# DigitalIO.net
KiCad netlist of a schematic drawn in Altium Designer
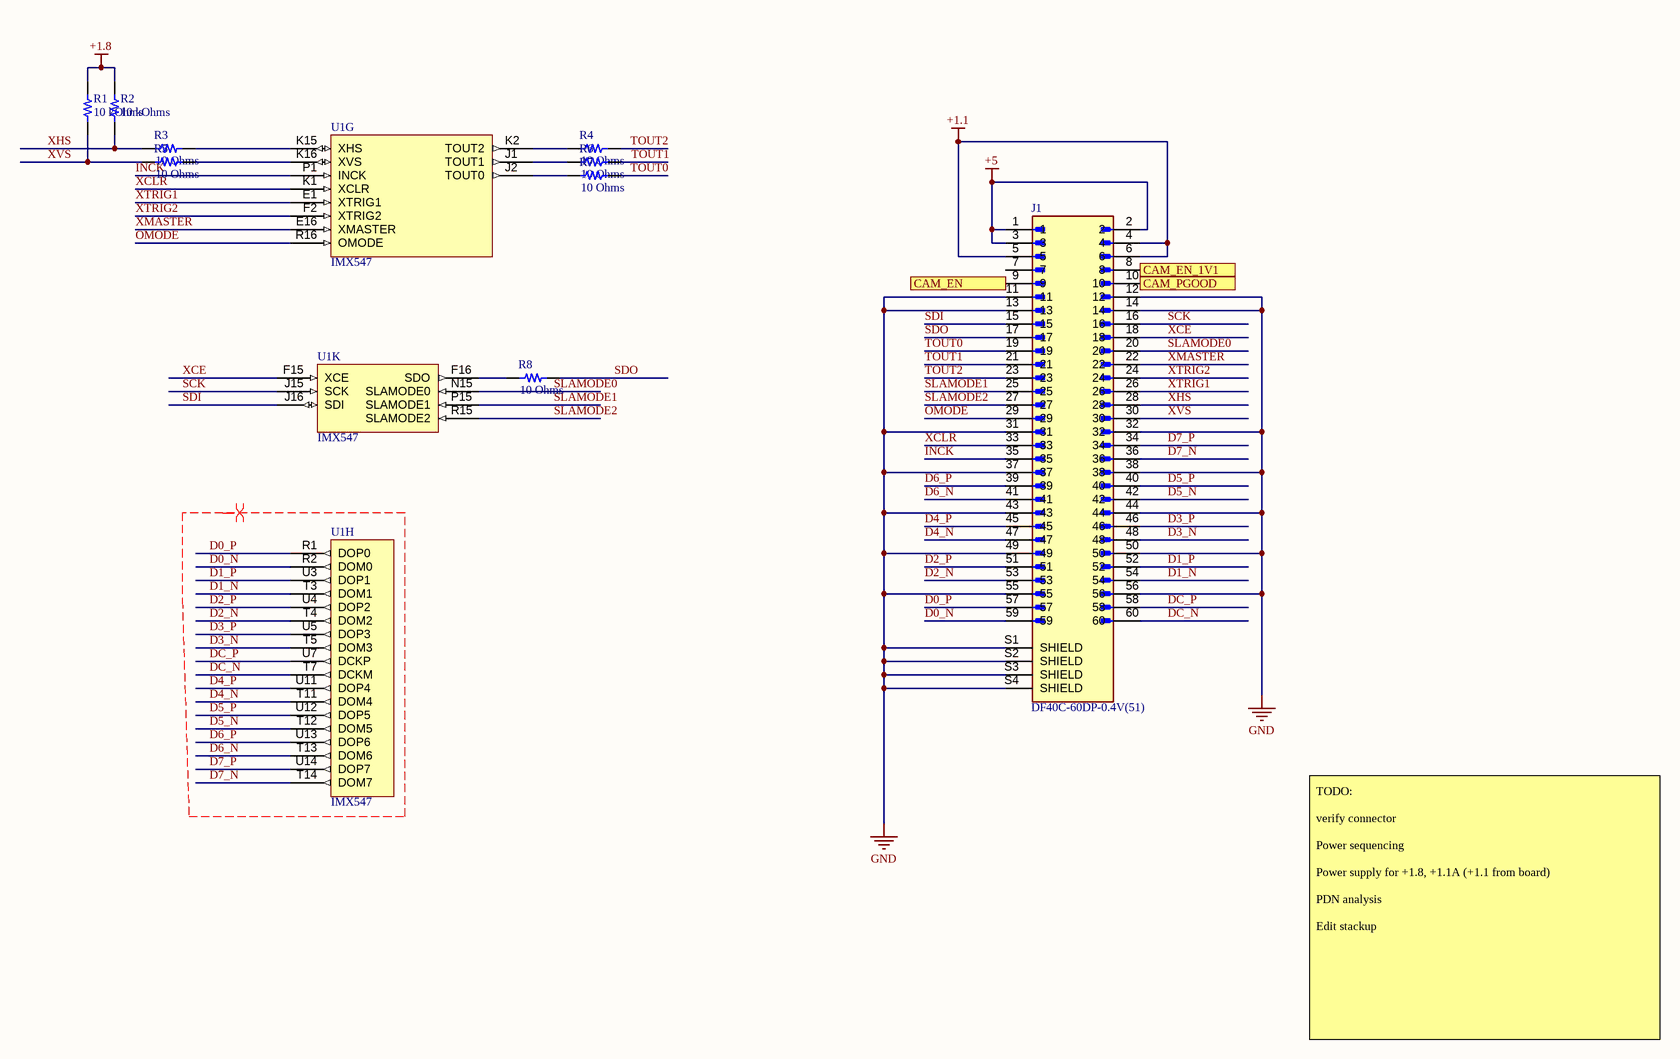
[diagram p0: DigitalIO.SchDoc]

(export (version "E")
  (design (tool "Eeschema 10.0.6"))
  (components
    (comp (ref "J1")
      (value "DF40C-60DP-0.4V(51)")
      (footprint "HIROSE_DF40C-60DP-0.4V(51)")
      (description "60 Position Connector Plug, Outer Shroud Contacts Surface Mount Gold")
      (fields (field (name "MF") "{'manufacturer': u'Hirose Electric'}"))
      (libsource (lib "qwe") (part "DF40C-60DP-0.4V(51)"))
    )
    (comp (ref "R1")
      (value "10 kOhms")
      (footprint "RES 0201_0603")
      (description "RES 10K OHM 5% 1/20W 0201")
      (fields
        (field (name "PART NUMBER") "RMCF0201JG10K0")
        (field (name "MANUFACTURER") "Stackpole Electronics Inc")
      )
      (libsource (lib "Celestial Altium Library - altium_library") (part "Resistor"))
    )
    (comp (ref "R2")
      (value "10 kOhms")
      (footprint "RES 0201_0603")
      (description "RES 10K OHM 5% 1/20W 0201")
      (fields
        (field (name "PART NUMBER") "RMCF0201JG10K0")
        (field (name "MANUFACTURER") "Stackpole Electronics Inc")
      )
      (libsource (lib "Celestial Altium Library - altium_library") (part "Resistor"))
    )
    (comp (ref "R3")
      (value "10 Ohms")
      (footprint "RES 0201_0603")
      (description "RES SMD 10 OHM 1% 1/20W 0201")
      (fields
        (field (name "PART NUMBER") "CRG0201F10R")
        (field (name "MANUFACTURER") "TE Connectivity Passive Product")
      )
      (libsource (lib "Celestial Altium Library - altium_library") (part "Resistor"))
    )
    (comp (ref "R4")
      (value "10 Ohms")
      (footprint "RES 0201_0603")
      (description "RES SMD 10 OHM 1% 1/20W 0201")
      (fields
        (field (name "PART NUMBER") "CRG0201F10R")
        (field (name "MANUFACTURER") "TE Connectivity Passive Product")
      )
      (libsource (lib "Celestial Altium Library - altium_library") (part "Resistor"))
    )
    (comp (ref "R5")
      (value "10 Ohms")
      (footprint "RES 0201_0603")
      (description "RES SMD 10 OHM 1% 1/20W 0201")
      (fields
        (field (name "PART NUMBER") "CRG0201F10R")
        (field (name "MANUFACTURER") "TE Connectivity Passive Product")
      )
      (libsource (lib "Celestial Altium Library - altium_library") (part "Resistor"))
    )
    (comp (ref "R6")
      (value "10 Ohms")
      (footprint "RES 0201_0603")
      (description "RES SMD 10 OHM 1% 1/20W 0201")
      (fields
        (field (name "PART NUMBER") "CRG0201F10R")
        (field (name "MANUFACTURER") "TE Connectivity Passive Product")
      )
      (libsource (lib "Celestial Altium Library - altium_library") (part "Resistor"))
    )
    (comp (ref "R7")
      (value "10 Ohms")
      (footprint "RES 0201_0603")
      (description "RES SMD 10 OHM 1% 1/20W 0201")
      (fields
        (field (name "PART NUMBER") "CRG0201F10R")
        (field (name "MANUFACTURER") "TE Connectivity Passive Product")
      )
      (libsource (lib "Celestial Altium Library - altium_library") (part "Resistor"))
    )
    (comp (ref "R8")
      (value "10 Ohms")
      (footprint "RES 0201_0603")
      (description "RES SMD 10 OHM 1% 1/20W 0201")
      (fields
        (field (name "PART NUMBER") "CRG0201F10R")
        (field (name "MANUFACTURER") "TE Connectivity Passive Product")
      )
      (libsource (lib "Celestial Altium Library - altium_library") (part "Resistor"))
    )
    (comp (ref "U1")
      (value "IMX547")
      (footprint "LGA230C100P16X17_1680X2000X260")
      (description "Sony IMX547 sensor")
      (libsource (lib "David Kräutmann Beratung") (part "IMX547"))
    )
  )
  (nets
    (net (code "1") (name "+1.1") (class "Default")
      (node (ref "J1") (pin "4") (pinfunction "4_4") (pintype "passive"))
      (node (ref "J1") (pin "5") (pinfunction "5_5") (pintype "passive"))
      (node (ref "J1") (pin "6") (pinfunction "6_6") (pintype "passive"))
    )
    (net (code "2") (name "+1.8") (class "Default")
      (node (ref "R1") (pin "2") (pinfunction "2_2") (pintype "passive"))
      (node (ref "R2") (pin "2") (pinfunction "2_2") (pintype "passive"))
    )
    (net (code "3") (name "+5") (class "Default")
      (node (ref "J1") (pin "1") (pinfunction "1_1") (pintype "passive"))
      (node (ref "J1") (pin "2") (pinfunction "2_2") (pintype "passive"))
      (node (ref "J1") (pin "3") (pinfunction "3_3") (pintype "passive"))
    )
    (net (code "4") (name "/CAM_EN") (class "Default")
      (node (ref "J1") (pin "9") (pinfunction "9_9") (pintype "passive"))
    )
    (net (code "5") (name "/CAM_EN_1V1") (class "Default")
      (node (ref "J1") (pin "8") (pinfunction "8_8") (pintype "passive"))
    )
    (net (code "6") (name "/CAM_PGOOD") (class "Default")
      (node (ref "J1") (pin "10") (pinfunction "10_10") (pintype "passive"))
    )
    (net (code "7") (name "/D0_N") (class "Default")
      (node (ref "J1") (pin "59") (pinfunction "59_59") (pintype "passive"))
      (node (ref "U1") (pin "R2") (pinfunction "DOM0_R2") (pintype "output"))
    )
    (net (code "8") (name "/D0_P") (class "Default")
      (node (ref "J1") (pin "57") (pinfunction "57_57") (pintype "passive"))
      (node (ref "U1") (pin "R1") (pinfunction "DOP0_R1") (pintype "output"))
    )
    (net (code "9") (name "/D1_N") (class "Default")
      (node (ref "J1") (pin "54") (pinfunction "54_54") (pintype "passive"))
      (node (ref "U1") (pin "T3") (pinfunction "DOM1_T3") (pintype "output"))
    )
    (net (code "10") (name "/D1_P") (class "Default")
      (node (ref "J1") (pin "52") (pinfunction "52_52") (pintype "passive"))
      (node (ref "U1") (pin "U3") (pinfunction "DOP1_U3") (pintype "output"))
    )
    (net (code "11") (name "/D2_N") (class "Default")
      (node (ref "J1") (pin "53") (pinfunction "53_53") (pintype "passive"))
      (node (ref "U1") (pin "T4") (pinfunction "DOM2_T4") (pintype "output"))
    )
    (net (code "12") (name "/D2_P") (class "Default")
      (node (ref "J1") (pin "51") (pinfunction "51_51") (pintype "passive"))
      (node (ref "U1") (pin "U4") (pinfunction "DOP2_U4") (pintype "output"))
    )
    (net (code "13") (name "/D3_N") (class "Default")
      (node (ref "J1") (pin "48") (pinfunction "48_48") (pintype "passive"))
      (node (ref "U1") (pin "T5") (pinfunction "DOM3_T5") (pintype "output"))
    )
    (net (code "14") (name "/D3_P") (class "Default")
      (node (ref "J1") (pin "46") (pinfunction "46_46") (pintype "passive"))
      (node (ref "U1") (pin "U5") (pinfunction "DOP3_U5") (pintype "output"))
    )
    (net (code "15") (name "/D4_N") (class "Default")
      (node (ref "J1") (pin "47") (pinfunction "47_47") (pintype "passive"))
      (node (ref "U1") (pin "T11") (pinfunction "DOM4_T11") (pintype "output"))
    )
    (net (code "16") (name "/D4_P") (class "Default")
      (node (ref "J1") (pin "45") (pinfunction "45_45") (pintype "passive"))
      (node (ref "U1") (pin "U11") (pinfunction "DOP4_U11") (pintype "output"))
    )
    (net (code "17") (name "/D5_N") (class "Default")
      (node (ref "J1") (pin "42") (pinfunction "42_42") (pintype "passive"))
      (node (ref "U1") (pin "T12") (pinfunction "DOM5_T12") (pintype "output"))
    )
    (net (code "18") (name "/D5_P") (class "Default")
      (node (ref "J1") (pin "40") (pinfunction "40_40") (pintype "passive"))
      (node (ref "U1") (pin "U12") (pinfunction "DOP5_U12") (pintype "output"))
    )
    (net (code "19") (name "/D6_N") (class "Default")
      (node (ref "J1") (pin "41") (pinfunction "41_41") (pintype "passive"))
      (node (ref "U1") (pin "T13") (pinfunction "DOM6_T13") (pintype "output"))
    )
    (net (code "20") (name "/D6_P") (class "Default")
      (node (ref "J1") (pin "39") (pinfunction "39_39") (pintype "passive"))
      (node (ref "U1") (pin "U13") (pinfunction "DOP6_U13") (pintype "output"))
    )
    (net (code "21") (name "/D7_N") (class "Default")
      (node (ref "J1") (pin "36") (pinfunction "36_36") (pintype "passive"))
      (node (ref "U1") (pin "T14") (pinfunction "DOM7_T14") (pintype "output"))
    )
    (net (code "22") (name "/D7_P") (class "Default")
      (node (ref "J1") (pin "34") (pinfunction "34_34") (pintype "passive"))
      (node (ref "U1") (pin "U14") (pinfunction "DOP7_U14") (pintype "output"))
    )
    (net (code "23") (name "/DC_N") (class "Default")
      (node (ref "J1") (pin "60") (pinfunction "60_60") (pintype "passive"))
      (node (ref "U1") (pin "T7") (pinfunction "DCKM_T7") (pintype "output"))
    )
    (net (code "24") (name "/DC_P") (class "Default")
      (node (ref "J1") (pin "58") (pinfunction "58_58") (pintype "passive"))
      (node (ref "U1") (pin "U7") (pinfunction "DCKP_U7") (pintype "output"))
    )
    (net (code "25") (name "/INCK") (class "Default")
      (node (ref "J1") (pin "35") (pinfunction "35_35") (pintype "passive"))
      (node (ref "U1") (pin "P1") (pinfunction "INCK_P1") (pintype "input"))
    )
    (net (code "26") (name "/OMODE") (class "Default")
      (node (ref "J1") (pin "29") (pinfunction "29_29") (pintype "passive"))
      (node (ref "U1") (pin "R16") (pinfunction "OMODE_R16") (pintype "input"))
    )
    (net (code "27") (name "/SCK") (class "Default")
      (node (ref "J1") (pin "16") (pinfunction "16_16") (pintype "passive"))
      (node (ref "U1") (pin "J15") (pinfunction "SCK_J15") (pintype "input"))
    )
    (net (code "28") (name "/SDI") (class "Default")
      (node (ref "J1") (pin "15") (pinfunction "15_15") (pintype "passive"))
      (node (ref "U1") (pin "J16") (pinfunction "SDI_J16") (pintype "bidirectional"))
    )
    (net (code "29") (name "/SDO") (class "Default")
      (node (ref "J1") (pin "17") (pinfunction "17_17") (pintype "passive"))
      (node (ref "R8") (pin "2") (pinfunction "2_2") (pintype "passive"))
    )
    (net (code "30") (name "/SLAMODE0") (class "Default")
      (node (ref "J1") (pin "20") (pinfunction "20_20") (pintype "passive"))
      (node (ref "U1") (pin "N15") (pinfunction "SLAMODE0_N15") (pintype "input"))
    )
    (net (code "31") (name "/SLAMODE1") (class "Default")
      (node (ref "J1") (pin "25") (pinfunction "25_25") (pintype "passive"))
      (node (ref "U1") (pin "P15") (pinfunction "SLAMODE1_P15") (pintype "input"))
    )
    (net (code "32") (name "/SLAMODE2") (class "Default")
      (node (ref "J1") (pin "27") (pinfunction "27_27") (pintype "passive"))
      (node (ref "U1") (pin "R15") (pinfunction "SLAMODE2_R15") (pintype "input"))
    )
    (net (code "33") (name "/TOUT0") (class "Default")
      (node (ref "J1") (pin "19") (pinfunction "19_19") (pintype "passive"))
      (node (ref "R7") (pin "2") (pinfunction "2_2") (pintype "passive"))
    )
    (net (code "34") (name "/TOUT1") (class "Default")
      (node (ref "J1") (pin "21") (pinfunction "21_21") (pintype "passive"))
      (node (ref "R6") (pin "2") (pinfunction "2_2") (pintype "passive"))
    )
    (net (code "35") (name "/TOUT2") (class "Default")
      (node (ref "J1") (pin "23") (pinfunction "23_23") (pintype "passive"))
      (node (ref "R4") (pin "2") (pinfunction "2_2") (pintype "passive"))
    )
    (net (code "36") (name "/XCE") (class "Default")
      (node (ref "J1") (pin "18") (pinfunction "18_18") (pintype "passive"))
      (node (ref "U1") (pin "F15") (pinfunction "XCE_F15") (pintype "input"))
    )
    (net (code "37") (name "/XCLR") (class "Default")
      (node (ref "J1") (pin "33") (pinfunction "33_33") (pintype "passive"))
      (node (ref "U1") (pin "K1") (pinfunction "XCLR_K1") (pintype "input"))
    )
    (net (code "38") (name "/XHS") (class "Default")
      (node (ref "J1") (pin "28") (pinfunction "28_28") (pintype "passive"))
      (node (ref "R2") (pin "1") (pinfunction "1_1") (pintype "passive"))
      (node (ref "R3") (pin "1") (pinfunction "1_1") (pintype "passive"))
    )
    (net (code "39") (name "/XMASTER") (class "Default")
      (node (ref "J1") (pin "22") (pinfunction "22_22") (pintype "passive"))
      (node (ref "U1") (pin "E16") (pinfunction "XMASTER_E16") (pintype "input"))
    )
    (net (code "40") (name "/XTRIG1") (class "Default")
      (node (ref "J1") (pin "26") (pinfunction "26_26") (pintype "passive"))
      (node (ref "U1") (pin "E1") (pinfunction "XTRIG1_E1") (pintype "input"))
    )
    (net (code "41") (name "/XTRIG2") (class "Default")
      (node (ref "J1") (pin "24") (pinfunction "24_24") (pintype "passive"))
      (node (ref "U1") (pin "F2") (pinfunction "XTRIG2_F2") (pintype "input"))
    )
    (net (code "42") (name "/XVS") (class "Default")
      (node (ref "J1") (pin "30") (pinfunction "30_30") (pintype "passive"))
      (node (ref "R1") (pin "1") (pinfunction "1_1") (pintype "passive"))
      (node (ref "R5") (pin "1") (pinfunction "1_1") (pintype "passive"))
    )
    (net (code "43") (name "GND") (class "Default")
      (node (ref "J1") (pin "11") (pinfunction "11_11") (pintype "passive"))
      (node (ref "J1") (pin "12") (pinfunction "12_12") (pintype "passive"))
      (node (ref "J1") (pin "13") (pinfunction "13_13") (pintype "passive"))
      (node (ref "J1") (pin "14") (pinfunction "14_14") (pintype "passive"))
      (node (ref "J1") (pin "31") (pinfunction "31_31") (pintype "passive"))
      (node (ref "J1") (pin "32") (pinfunction "32_32") (pintype "passive"))
      (node (ref "J1") (pin "37") (pinfunction "37_37") (pintype "passive"))
      (node (ref "J1") (pin "38") (pinfunction "38_38") (pintype "passive"))
      (node (ref "J1") (pin "43") (pinfunction "43_43") (pintype "passive"))
      (node (ref "J1") (pin "44") (pinfunction "44_44") (pintype "passive"))
      (node (ref "J1") (pin "49") (pinfunction "49_49") (pintype "passive"))
      (node (ref "J1") (pin "50") (pinfunction "50_50") (pintype "passive"))
      (node (ref "J1") (pin "55") (pinfunction "55_55") (pintype "passive"))
      (node (ref "J1") (pin "56") (pinfunction "56_56") (pintype "passive"))
      (node (ref "J1") (pin "S1") (pinfunction "SHIELD_S1") (pintype "passive"))
      (node (ref "J1") (pin "S2") (pinfunction "SHIELD_S2") (pintype "passive"))
      (node (ref "J1") (pin "S3") (pinfunction "SHIELD_S3") (pintype "passive"))
      (node (ref "J1") (pin "S4") (pinfunction "SHIELD_S4") (pintype "passive"))
    )
    (net (code "44") (name "Net-(U1G-TOUT0)") (class "Default")
      (node (ref "R7") (pin "1") (pinfunction "1_1") (pintype "passive"))
      (node (ref "U1") (pin "J2") (pinfunction "TOUT0_J2") (pintype "output"))
    )
    (net (code "45") (name "Net-(U1G-TOUT1)") (class "Default")
      (node (ref "R6") (pin "1") (pinfunction "1_1") (pintype "passive"))
      (node (ref "U1") (pin "J1") (pinfunction "TOUT1_J1") (pintype "output"))
    )
    (net (code "46") (name "Net-(U1G-TOUT2)") (class "Default")
      (node (ref "R4") (pin "1") (pinfunction "1_1") (pintype "passive"))
      (node (ref "U1") (pin "K2") (pinfunction "TOUT2_K2") (pintype "output"))
    )
    (net (code "47") (name "Net-(U1G-XHS)") (class "Default")
      (node (ref "R3") (pin "2") (pinfunction "2_2") (pintype "passive"))
      (node (ref "U1") (pin "K15") (pinfunction "XHS_K15") (pintype "bidirectional"))
    )
    (net (code "48") (name "Net-(U1G-XVS)") (class "Default")
      (node (ref "R5") (pin "2") (pinfunction "2_2") (pintype "passive"))
      (node (ref "U1") (pin "K16") (pinfunction "XVS_K16") (pintype "bidirectional"))
    )
    (net (code "49") (name "Net-(U1K-SDO)") (class "Default")
      (node (ref "R8") (pin "1") (pinfunction "1_1") (pintype "passive"))
      (node (ref "U1") (pin "F16") (pinfunction "SDO_F16") (pintype "output"))
    )
    (net (code "50") (name "unconnected-(J1-Pad7)") (class "Default")
      (node (ref "J1") (pin "7") (pinfunction "7_7") (pintype "passive"))
    )
  )
)
